# dps_YZ.net
KiCad netlist of a schematic drawn in EAGLE
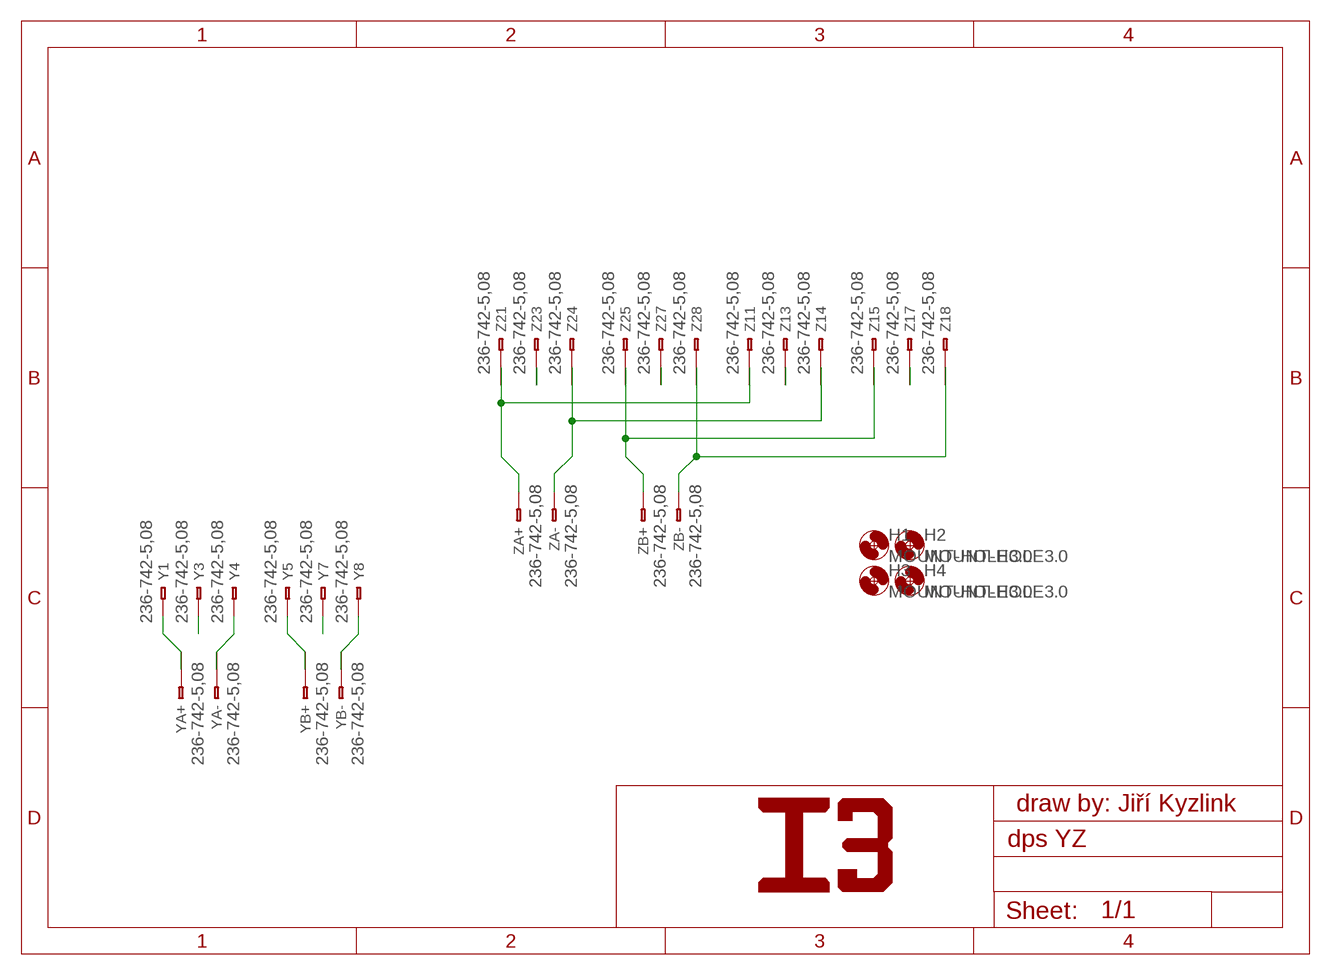
[diagram p0: schematic, sheet 1]

(export (version "E")
  (design (tool "Eeschema 10.0.6"))
  (components
    (comp (ref "H1")
      (value "MOUNT-HOLE3.0")
      (footprint "eagle-import:3,0")
      (libsource (lib "eagle-import") (part "MOUNT-HOLE3.0"))
    )
    (comp (ref "H2")
      (value "MOUNT-HOLE3.0")
      (footprint "eagle-import:3,0")
      (libsource (lib "eagle-import") (part "MOUNT-HOLE3.0"))
    )
    (comp (ref "H3")
      (value "MOUNT-HOLE3.0")
      (footprint "eagle-import:3,0")
      (libsource (lib "eagle-import") (part "MOUNT-HOLE3.0"))
    )
    (comp (ref "H4")
      (value "MOUNT-HOLE3.0")
      (footprint "eagle-import:3,0")
      (libsource (lib "eagle-import") (part "MOUNT-HOLE3.0"))
    )
    (comp (ref "Y1")
      (value "236-742-5,08")
      (footprint "eagle-import:236-4XX")
      (libsource (lib "eagle-import") (part "236-5,08-742"))
    )
    (comp (ref "Y3")
      (value "236-742-5,08")
      (footprint "eagle-import:236-4XX")
      (libsource (lib "eagle-import") (part "236-5,08-742"))
    )
    (comp (ref "Y4")
      (value "236-742-5,08")
      (footprint "eagle-import:236-4XX")
      (libsource (lib "eagle-import") (part "236-5,08-742"))
    )
    (comp (ref "Y5")
      (value "236-742-5,08")
      (footprint "eagle-import:236-4XX")
      (libsource (lib "eagle-import") (part "236-5,08-742"))
    )
    (comp (ref "Y7")
      (value "236-742-5,08")
      (footprint "eagle-import:236-4XX")
      (libsource (lib "eagle-import") (part "236-5,08-742"))
    )
    (comp (ref "Y8")
      (value "236-742-5,08")
      (footprint "eagle-import:236-4XX")
      (libsource (lib "eagle-import") (part "236-5,08-742"))
    )
    (comp (ref "YA+")
      (value "236-742-5,08")
      (footprint "eagle-import:236-4XX")
      (libsource (lib "eagle-import") (part "236-5,08-742"))
    )
    (comp (ref "YA-")
      (value "236-742-5,08")
      (footprint "eagle-import:236-4XX")
      (libsource (lib "eagle-import") (part "236-5,08-742"))
    )
    (comp (ref "YB+")
      (value "236-742-5,08")
      (footprint "eagle-import:236-4XX")
      (libsource (lib "eagle-import") (part "236-5,08-742"))
    )
    (comp (ref "YB-")
      (value "236-742-5,08")
      (footprint "eagle-import:236-4XX")
      (libsource (lib "eagle-import") (part "236-5,08-742"))
    )
    (comp (ref "Z11")
      (value "236-742-5,08")
      (footprint "eagle-import:236-4XX")
      (libsource (lib "eagle-import") (part "236-5,08-742"))
    )
    (comp (ref "Z13")
      (value "236-742-5,08")
      (footprint "eagle-import:236-4XX")
      (libsource (lib "eagle-import") (part "236-5,08-742"))
    )
    (comp (ref "Z14")
      (value "236-742-5,08")
      (footprint "eagle-import:236-4XX")
      (libsource (lib "eagle-import") (part "236-5,08-742"))
    )
    (comp (ref "Z15")
      (value "236-742-5,08")
      (footprint "eagle-import:236-4XX")
      (libsource (lib "eagle-import") (part "236-5,08-742"))
    )
    (comp (ref "Z17")
      (value "236-742-5,08")
      (footprint "eagle-import:236-4XX")
      (libsource (lib "eagle-import") (part "236-5,08-742"))
    )
    (comp (ref "Z18")
      (value "236-742-5,08")
      (footprint "eagle-import:236-4XX")
      (libsource (lib "eagle-import") (part "236-5,08-742"))
    )
    (comp (ref "Z21")
      (value "236-742-5,08")
      (footprint "eagle-import:236-4XX")
      (libsource (lib "eagle-import") (part "236-5,08-742"))
    )
    (comp (ref "Z23")
      (value "236-742-5,08")
      (footprint "eagle-import:236-4XX")
      (libsource (lib "eagle-import") (part "236-5,08-742"))
    )
    (comp (ref "Z24")
      (value "236-742-5,08")
      (footprint "eagle-import:236-4XX")
      (libsource (lib "eagle-import") (part "236-5,08-742"))
    )
    (comp (ref "Z25")
      (value "236-742-5,08")
      (footprint "eagle-import:236-4XX")
      (libsource (lib "eagle-import") (part "236-5,08-742"))
    )
    (comp (ref "Z27")
      (value "236-742-5,08")
      (footprint "eagle-import:236-4XX")
      (libsource (lib "eagle-import") (part "236-5,08-742"))
    )
    (comp (ref "Z28")
      (value "236-742-5,08")
      (footprint "eagle-import:236-4XX")
      (libsource (lib "eagle-import") (part "236-5,08-742"))
    )
    (comp (ref "ZA+")
      (value "236-742-5,08")
      (footprint "eagle-import:236-4XX")
      (libsource (lib "eagle-import") (part "236-5,08-742"))
    )
    (comp (ref "ZA-")
      (value "236-742-5,08")
      (footprint "eagle-import:236-4XX")
      (libsource (lib "eagle-import") (part "236-5,08-742"))
    )
    (comp (ref "ZB+")
      (value "236-742-5,08")
      (footprint "eagle-import:236-4XX")
      (libsource (lib "eagle-import") (part "236-5,08-742"))
    )
    (comp (ref "ZB-")
      (value "236-742-5,08")
      (footprint "eagle-import:236-4XX")
      (libsource (lib "eagle-import") (part "236-5,08-742"))
    )
  )
  (nets
    (net (code "1") (name "Net-(Y1-A1)") (class "Default")
      (node (ref "Y1") (pin "1@1") (pinfunction "A1_1@1") (pintype "passive"))
      (node (ref "Y1") (pin "1@2") (pinfunction "B1_1@2") (pintype "passive"))
      (node (ref "YA+") (pin "1@1") (pinfunction "A1_1@1") (pintype "passive"))
      (node (ref "YA+") (pin "1@2") (pinfunction "B1_1@2") (pintype "passive"))
    )
    (net (code "2") (name "Net-(Y3-A1)") (class "Default")
      (node (ref "Y3") (pin "1@1") (pinfunction "A1_1@1") (pintype "passive"))
      (node (ref "Y3") (pin "1@2") (pinfunction "B1_1@2") (pintype "passive"))
    )
    (net (code "3") (name "Net-(Y4-A1)") (class "Default")
      (node (ref "Y4") (pin "1@1") (pinfunction "A1_1@1") (pintype "passive"))
      (node (ref "Y4") (pin "1@2") (pinfunction "B1_1@2") (pintype "passive"))
      (node (ref "YA-") (pin "1@1") (pinfunction "A1_1@1") (pintype "passive"))
      (node (ref "YA-") (pin "1@2") (pinfunction "B1_1@2") (pintype "passive"))
    )
    (net (code "4") (name "Net-(Y5-A1)") (class "Default")
      (node (ref "Y5") (pin "1@1") (pinfunction "A1_1@1") (pintype "passive"))
      (node (ref "Y5") (pin "1@2") (pinfunction "B1_1@2") (pintype "passive"))
      (node (ref "YB+") (pin "1@1") (pinfunction "A1_1@1") (pintype "passive"))
      (node (ref "YB+") (pin "1@2") (pinfunction "B1_1@2") (pintype "passive"))
    )
    (net (code "5") (name "Net-(Y7-A1)") (class "Default")
      (node (ref "Y7") (pin "1@1") (pinfunction "A1_1@1") (pintype "passive"))
      (node (ref "Y7") (pin "1@2") (pinfunction "B1_1@2") (pintype "passive"))
    )
    (net (code "6") (name "Net-(Y8-A1)") (class "Default")
      (node (ref "Y8") (pin "1@1") (pinfunction "A1_1@1") (pintype "passive"))
      (node (ref "Y8") (pin "1@2") (pinfunction "B1_1@2") (pintype "passive"))
      (node (ref "YB-") (pin "1@1") (pinfunction "A1_1@1") (pintype "passive"))
      (node (ref "YB-") (pin "1@2") (pinfunction "B1_1@2") (pintype "passive"))
    )
    (net (code "7") (name "Net-(Z11-A1)") (class "Default")
      (node (ref "Z11") (pin "1@1") (pinfunction "A1_1@1") (pintype "passive"))
      (node (ref "Z11") (pin "1@2") (pinfunction "B1_1@2") (pintype "passive"))
      (node (ref "Z21") (pin "1@1") (pinfunction "A1_1@1") (pintype "passive"))
      (node (ref "Z21") (pin "1@2") (pinfunction "B1_1@2") (pintype "passive"))
      (node (ref "ZA+") (pin "1@1") (pinfunction "A1_1@1") (pintype "passive"))
      (node (ref "ZA+") (pin "1@2") (pinfunction "B1_1@2") (pintype "passive"))
    )
    (net (code "8") (name "Net-(Z13-A1)") (class "Default")
      (node (ref "Z13") (pin "1@1") (pinfunction "A1_1@1") (pintype "passive"))
      (node (ref "Z13") (pin "1@2") (pinfunction "B1_1@2") (pintype "passive"))
    )
    (net (code "9") (name "Net-(Z14-A1)") (class "Default")
      (node (ref "Z14") (pin "1@1") (pinfunction "A1_1@1") (pintype "passive"))
      (node (ref "Z14") (pin "1@2") (pinfunction "B1_1@2") (pintype "passive"))
      (node (ref "Z24") (pin "1@1") (pinfunction "A1_1@1") (pintype "passive"))
      (node (ref "Z24") (pin "1@2") (pinfunction "B1_1@2") (pintype "passive"))
      (node (ref "ZA-") (pin "1@1") (pinfunction "A1_1@1") (pintype "passive"))
      (node (ref "ZA-") (pin "1@2") (pinfunction "B1_1@2") (pintype "passive"))
    )
    (net (code "10") (name "Net-(Z15-A1)") (class "Default")
      (node (ref "Z15") (pin "1@1") (pinfunction "A1_1@1") (pintype "passive"))
      (node (ref "Z15") (pin "1@2") (pinfunction "B1_1@2") (pintype "passive"))
      (node (ref "Z25") (pin "1@1") (pinfunction "A1_1@1") (pintype "passive"))
      (node (ref "Z25") (pin "1@2") (pinfunction "B1_1@2") (pintype "passive"))
      (node (ref "ZB+") (pin "1@1") (pinfunction "A1_1@1") (pintype "passive"))
      (node (ref "ZB+") (pin "1@2") (pinfunction "B1_1@2") (pintype "passive"))
    )
    (net (code "11") (name "Net-(Z17-A1)") (class "Default")
      (node (ref "Z17") (pin "1@1") (pinfunction "A1_1@1") (pintype "passive"))
      (node (ref "Z17") (pin "1@2") (pinfunction "B1_1@2") (pintype "passive"))
    )
    (net (code "12") (name "Net-(Z18-A1)") (class "Default")
      (node (ref "Z18") (pin "1@1") (pinfunction "A1_1@1") (pintype "passive"))
      (node (ref "Z18") (pin "1@2") (pinfunction "B1_1@2") (pintype "passive"))
      (node (ref "Z28") (pin "1@1") (pinfunction "A1_1@1") (pintype "passive"))
      (node (ref "Z28") (pin "1@2") (pinfunction "B1_1@2") (pintype "passive"))
      (node (ref "ZB-") (pin "1@1") (pinfunction "A1_1@1") (pintype "passive"))
      (node (ref "ZB-") (pin "1@2") (pinfunction "B1_1@2") (pintype "passive"))
    )
    (net (code "13") (name "Net-(Z23-A1)") (class "Default")
      (node (ref "Z23") (pin "1@1") (pinfunction "A1_1@1") (pintype "passive"))
      (node (ref "Z23") (pin "1@2") (pinfunction "B1_1@2") (pintype "passive"))
    )
    (net (code "14") (name "Net-(Z27-A1)") (class "Default")
      (node (ref "Z27") (pin "1@1") (pinfunction "A1_1@1") (pintype "passive"))
      (node (ref "Z27") (pin "1@2") (pinfunction "B1_1@2") (pintype "passive"))
    )
  )
)
